# Potentiostat_VREF.net
KiCad netlist of a schematic drawn in EAGLE
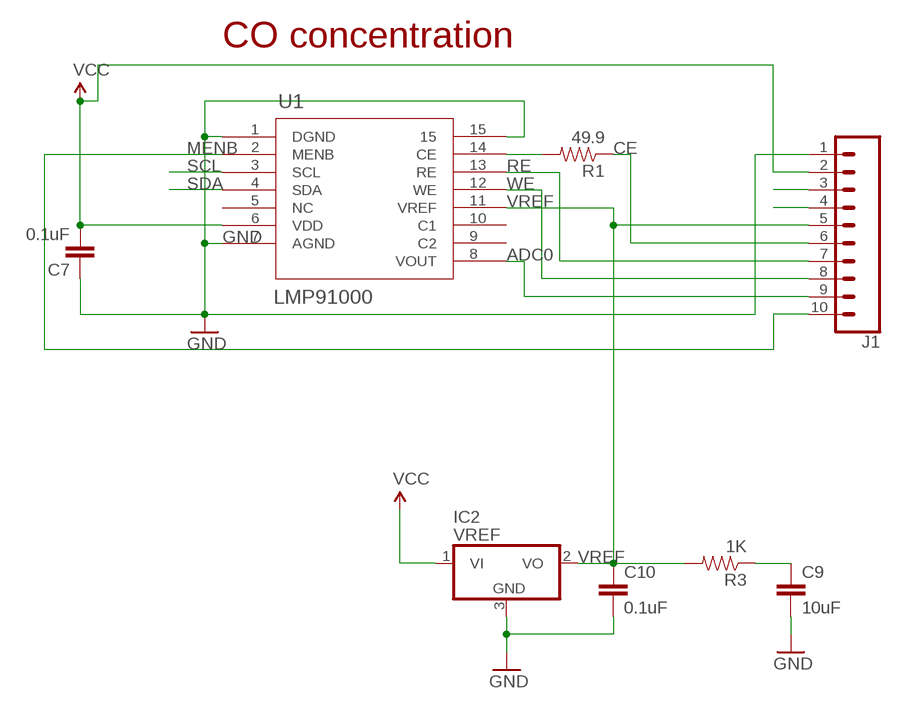
[diagram p0: schematic, sheet 1]

(export (version "E")
  (design (tool "Eeschema 10.0.6"))
  (components
    (comp (ref "C7")
      (value "0.1uF")
      (footprint "eagle-import:0805")
      (fields (field (name "MPN") "AC0805KRX7R9BB104"))
      (libsource (lib "eagle-import") (part "CAP0805"))
    )
    (comp (ref "C9")
      (value "10uF")
      (footprint "eagle-import:0805")
      (fields (field (name "MPN") "CC0805ZKY5V6BB106"))
      (libsource (lib "eagle-import") (part "CAP0805"))
    )
    (comp (ref "C10")
      (value "0.1uF")
      (footprint "eagle-import:0805")
      (fields (field (name "MPN") "AC0805KRX7R9BB104"))
      (libsource (lib "eagle-import") (part "CAP0805"))
    )
    (comp (ref "IC2")
      (value "VREF")
      (footprint "eagle-import:SOT23")
      (fields (field (name "MPN") "ISL60002DIH320Z-TK"))
      (libsource (lib "eagle-import") (part "ISL60002DIH320ZCB"))
    )
    (comp (ref "J1")
      (value "CONN_10\"")
      (footprint "eagle-import:1X10")
      (libsource (lib "eagle-import") (part "CONN_10{dblquote}"))
    )
    (comp (ref "R1")
      (value "49.9")
      (footprint "eagle-import:0805")
      (fields (field (name "MPN") "RC0805FR-0749R9L"))
      (libsource (lib "eagle-import") (part "RESISTOR0805-RES"))
    )
    (comp (ref "R3")
      (value "1K")
      (footprint "eagle-import:0805")
      (fields (field (name "MPN") "RC0805JR-071KL"))
      (libsource (lib "eagle-import") (part "RESISTOR0805-RES"))
    )
    (comp (ref "U1")
      (value "LMP91000")
      (footprint "eagle-import:SDA14B")
      (fields
        (field (name "MANUFACTURER") "Texas Instruments")
        (field (name "MANUFACTURER_PART_NUMBER") "lmp91000_nhl_14")
      )
      (libsource (lib "eagle-import") (part "LMP91000_NHL_14"))
    )
  )
  (nets
    (net (code "1") (name "/ADC0") (class "Default")
      (node (ref "J1") (pin "9") (pinfunction "9_9") (pintype "passive"))
      (node (ref "U1") (pin "8") (pinfunction "VOUT_8") (pintype "output"))
    )
    (net (code "2") (name "/CE") (class "Default")
      (node (ref "J1") (pin "6") (pinfunction "6_6") (pintype "passive"))
      (node (ref "R1") (pin "1") (pinfunction "1_1") (pintype "passive"))
    )
    (net (code "3") (name "/MENB") (class "Default")
      (node (ref "J1") (pin "10") (pinfunction "10_10") (pintype "passive"))
      (node (ref "U1") (pin "2") (pinfunction "MENB_2") (pintype "passive"))
    )
    (net (code "4") (name "/RE") (class "Default")
      (node (ref "J1") (pin "7") (pinfunction "7_7") (pintype "passive"))
      (node (ref "U1") (pin "13") (pinfunction "RE_13") (pintype "input"))
    )
    (net (code "5") (name "/SCL") (class "Default")
      (node (ref "U1") (pin "3") (pinfunction "SCL_3") (pintype "passive"))
    )
    (net (code "6") (name "/SDA") (class "Default")
      (node (ref "U1") (pin "4") (pinfunction "SDA_4") (pintype "passive"))
    )
    (net (code "7") (name "/VREF") (class "Default")
      (node (ref "C10") (pin "1") (pinfunction "1_1") (pintype "passive"))
      (node (ref "IC2") (pin "2") (pinfunction "VO_2") (pintype "passive"))
      (node (ref "J1") (pin "5") (pinfunction "5_5") (pintype "passive"))
      (node (ref "R3") (pin "2") (pinfunction "2_2") (pintype "passive"))
      (node (ref "U1") (pin "11") (pinfunction "VREF_11") (pintype "input"))
    )
    (net (code "8") (name "/WE") (class "Default")
      (node (ref "J1") (pin "8") (pinfunction "8_8") (pintype "passive"))
      (node (ref "U1") (pin "12") (pinfunction "WE_12") (pintype "output"))
    )
    (net (code "9") (name "GND") (class "Default")
      (node (ref "C10") (pin "2") (pinfunction "2_2") (pintype "passive"))
      (node (ref "C7") (pin "1") (pinfunction "1_1") (pintype "passive"))
      (node (ref "C9") (pin "2") (pinfunction "2_2") (pintype "passive"))
      (node (ref "IC2") (pin "3") (pinfunction "GND_3") (pintype "passive"))
      (node (ref "J1") (pin "1") (pinfunction "1_1") (pintype "passive"))
      (node (ref "U1") (pin "1") (pinfunction "DGND_1") (pintype "power_in"))
      (node (ref "U1") (pin "15") (pinfunction "15_15") (pintype "passive"))
      (node (ref "U1") (pin "7") (pinfunction "AGND_7") (pintype "power_in"))
    )
    (net (code "10") (name "Net-(C9-Pad1)") (class "Default")
      (node (ref "C9") (pin "1") (pinfunction "1_1") (pintype "passive"))
      (node (ref "R3") (pin "1") (pinfunction "1_1") (pintype "passive"))
    )
    (net (code "11") (name "Net-(U1-CE)") (class "Default")
      (node (ref "R1") (pin "2") (pinfunction "2_2") (pintype "passive"))
      (node (ref "U1") (pin "14") (pinfunction "CE_14") (pintype "output"))
    )
    (net (code "12") (name "VCC") (class "Default")
      (node (ref "C7") (pin "2") (pinfunction "2_2") (pintype "passive"))
      (node (ref "IC2") (pin "1") (pinfunction "VI_1") (pintype "input"))
      (node (ref "J1") (pin "2") (pinfunction "2_2") (pintype "passive"))
      (node (ref "U1") (pin "6") (pinfunction "VDD_6") (pintype "power_in"))
    )
    (net (code "13") (name "unconnected-(J1-Pad3)") (class "Default")
      (node (ref "J1") (pin "3") (pinfunction "3_3") (pintype "passive"))
    )
    (net (code "14") (name "unconnected-(J1-Pad4)") (class "Default")
      (node (ref "J1") (pin "4") (pinfunction "4_4") (pintype "passive"))
    )
    (net (code "15") (name "unconnected-(U1-C1-Pad10)") (class "Default")
      (node (ref "U1") (pin "10") (pinfunction "C1_10") (pintype "passive"))
    )
    (net (code "16") (name "unconnected-(U1-C2-Pad9)") (class "Default")
      (node (ref "U1") (pin "9") (pinfunction "C2_9") (pintype "passive"))
    )
    (net (code "17") (name "unconnected-(U1-NC-Pad5)") (class "Default")
      (node (ref "U1") (pin "5") (pinfunction "NC_5") (pintype "no_connect"))
    )
  )
)
